# 2relay.net
KiCad netlist of a schematic drawn in EAGLE
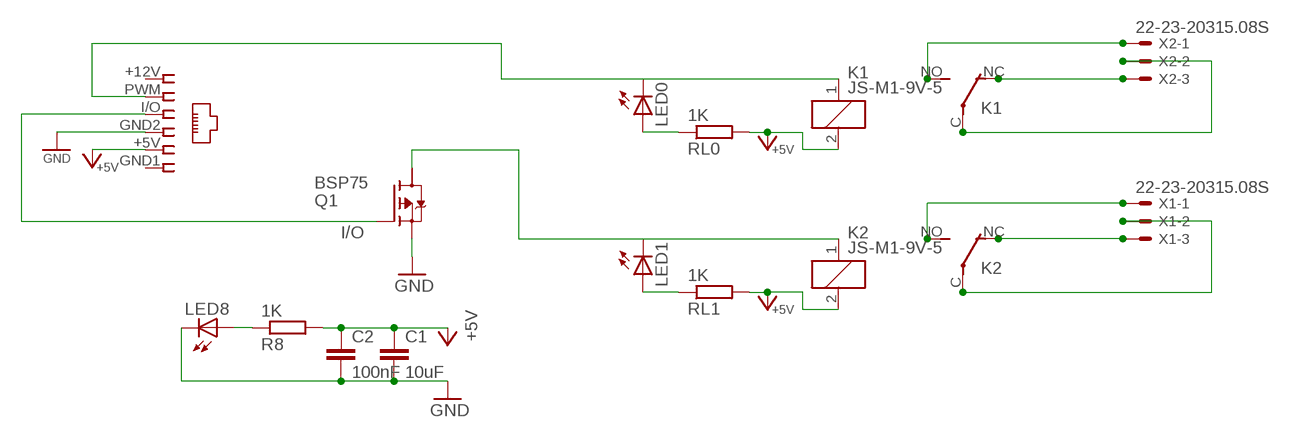
[diagram p0: schematic, sheet 1]

(export (version "E")
  (design (tool "Eeschema 10.0.6"))
  (components
    (comp (ref "C1")
      (value "10uF")
      (footprint "eagle-import:C1206")
      (libsource (lib "eagle-import") (part "C-EUC1206"))
    )
    (comp (ref "C2")
      (value "100nF")
      (footprint "eagle-import:C1206")
      (libsource (lib "eagle-import") (part "C-EUC1206"))
    )
    (comp (ref "I/O_PWM")
      (value "I2C 1")
      (footprint "eagle-import:RJ12-STRAIGHT")
      (libsource (lib "eagle-import") (part "RJ12STRAIGHT"))
    )
    (comp (ref "K1")
      (value "JS-M1-9V-5")
      (footprint "eagle-import:JS-M")
      (libsource (lib "eagle-import") (part "JS-M1-9V-5"))
    )
    (comp (ref "K2")
      (value "JS-M1-9V-5")
      (footprint "eagle-import:JS-M")
      (libsource (lib "eagle-import") (part "JS-M1-9V-5"))
    )
    (comp (ref "LED0")
      (value "LED1206")
      (footprint "eagle-import:LED-1206")
      (libsource (lib "eagle-import") (part "LED1206"))
    )
    (comp (ref "LED1")
      (value "LED1206")
      (footprint "eagle-import:LED-1206")
      (libsource (lib "eagle-import") (part "LED1206"))
    )
    (comp (ref "LED8")
      (value "LED1206")
      (footprint "eagle-import:LED-1206")
      (libsource (lib "eagle-import") (part "LED1206"))
    )
    (comp (ref "Q1")
      (value "BSP75")
      (footprint "eagle-import:PG-SOT-223")
      (libsource (lib "eagle-import") (part "BSP613P"))
    )
    (comp (ref "R8")
      (value "1K")
      (footprint "eagle-import:M1206")
      (libsource (lib "eagle-import") (part "R-EU_M1206"))
    )
    (comp (ref "RL0")
      (value "1K")
      (footprint "eagle-import:M1206")
      (libsource (lib "eagle-import") (part "R-EU_M1206"))
    )
    (comp (ref "RL1")
      (value "1K")
      (footprint "eagle-import:M1206")
      (libsource (lib "eagle-import") (part "R-EU_M1206"))
    )
    (comp (ref "X1")
      (value "22-23-20315.08S")
      (footprint "eagle-import:3-PIN-5.08S")
      (libsource (lib "eagle-import") (part "22-23-20315.08S"))
    )
    (comp (ref "X2")
      (value "22-23-20315.08S")
      (footprint "eagle-import:3-PIN-5.08S")
      (libsource (lib "eagle-import") (part "22-23-20315.08S"))
    )
  )
  (nets
    (net (code "1") (name "+5V") (class "Default")
      (node (ref "C1") (pin "1") (pinfunction "1_1") (pintype "passive"))
      (node (ref "C2") (pin "1") (pinfunction "1_1") (pintype "passive"))
      (node (ref "I/O_PWM") (pin "+5V") (pinfunction "5_+5V") (pintype "bidirectional"))
      (node (ref "K1") (pin "2") (pinfunction "2_2") (pintype "passive"))
      (node (ref "K2") (pin "2") (pinfunction "2_2") (pintype "passive"))
      (node (ref "R8") (pin "2") (pinfunction "2_2") (pintype "passive"))
      (node (ref "RL0") (pin "2") (pinfunction "2_2") (pintype "passive"))
      (node (ref "RL1") (pin "2") (pinfunction "2_2") (pintype "passive"))
    )
    (net (code "2") (name "/I{slash}O") (class "Default")
      (node (ref "I/O_PWM") (pin "I/O") (pinfunction "3_I/O") (pintype "bidirectional"))
      (node (ref "Q1") (pin "1") (pinfunction "G_1") (pintype "passive"))
    )
    (net (code "3") (name "GND") (class "Default")
      (node (ref "C1") (pin "2") (pinfunction "2_2") (pintype "passive"))
      (node (ref "C2") (pin "2") (pinfunction "2_2") (pintype "passive"))
      (node (ref "I/O_PWM") (pin "GND2") (pinfunction "4_GND2") (pintype "bidirectional"))
      (node (ref "LED8") (pin "C") (pinfunction "C_C") (pintype "passive"))
      (node (ref "Q1") (pin "3") (pinfunction "S_3") (pintype "passive"))
    )
    (net (code "4") (name "Net-(I/O_PWM-2)") (class "Default")
      (node (ref "I/O_PWM") (pin "PWM") (pinfunction "2_PWM") (pintype "bidirectional"))
      (node (ref "K1") (pin "1") (pinfunction "1_1") (pintype "passive"))
      (node (ref "LED0") (pin "C") (pinfunction "C_C") (pintype "passive"))
    )
    (net (code "5") (name "Net-(K1B-O)") (class "Default")
      (node (ref "K1") (pin "NC") (pinfunction "O_NC") (pintype "passive"))
      (node (ref "X2") (pin "3") (pinfunction "S_3") (pintype "passive"))
    )
    (net (code "6") (name "Net-(K1B-P)") (class "Default")
      (node (ref "K1") (pin "C") (pinfunction "P_C") (pintype "passive"))
      (node (ref "X2") (pin "2") (pinfunction "S_2") (pintype "passive"))
    )
    (net (code "7") (name "Net-(K1B-S)") (class "Default")
      (node (ref "K1") (pin "NO") (pinfunction "S_NO") (pintype "passive"))
      (node (ref "X2") (pin "1") (pinfunction "S_1") (pintype "passive"))
    )
    (net (code "8") (name "Net-(K2-Pad1)") (class "Default")
      (node (ref "K2") (pin "1") (pinfunction "1_1") (pintype "passive"))
      (node (ref "LED1") (pin "C") (pinfunction "C_C") (pintype "passive"))
      (node (ref "Q1") (pin "2") (pinfunction "D_2") (pintype "passive"))
    )
    (net (code "9") (name "Net-(K2B-O)") (class "Default")
      (node (ref "K2") (pin "NC") (pinfunction "O_NC") (pintype "passive"))
      (node (ref "X1") (pin "3") (pinfunction "S_3") (pintype "passive"))
    )
    (net (code "10") (name "Net-(K2B-P)") (class "Default")
      (node (ref "K2") (pin "C") (pinfunction "P_C") (pintype "passive"))
      (node (ref "X1") (pin "2") (pinfunction "S_2") (pintype "passive"))
    )
    (net (code "11") (name "Net-(K2B-S)") (class "Default")
      (node (ref "K2") (pin "NO") (pinfunction "S_NO") (pintype "passive"))
      (node (ref "X1") (pin "1") (pinfunction "S_1") (pintype "passive"))
    )
    (net (code "12") (name "Net-(LED0-PadA)") (class "Default")
      (node (ref "LED0") (pin "A") (pinfunction "A_A") (pintype "passive"))
      (node (ref "RL0") (pin "1") (pinfunction "1_1") (pintype "passive"))
    )
    (net (code "13") (name "Net-(LED1-PadA)") (class "Default")
      (node (ref "LED1") (pin "A") (pinfunction "A_A") (pintype "passive"))
      (node (ref "RL1") (pin "1") (pinfunction "1_1") (pintype "passive"))
    )
    (net (code "14") (name "Net-(LED8-PadA)") (class "Default")
      (node (ref "LED8") (pin "A") (pinfunction "A_A") (pintype "passive"))
      (node (ref "R8") (pin "1") (pinfunction "1_1") (pintype "passive"))
    )
    (net (code "15") (name "unconnected-(I/O_PWM-1-Pad+12V)") (class "Default")
      (node (ref "I/O_PWM") (pin "+12V") (pinfunction "1_+12V") (pintype "bidirectional"))
    )
    (net (code "16") (name "unconnected-(I/O_PWM-6-PadGND1)") (class "Default")
      (node (ref "I/O_PWM") (pin "GND1") (pinfunction "6_GND1") (pintype "bidirectional"))
    )
    (net (code "17") (name "unconnected-(Q1-D-Pad4)") (class "Default")
      (node (ref "Q1") (pin "4") (pinfunction "D_4") (pintype "passive"))
    )
  )
)
